# AntennaPCB.net
KiCad netlist of a schematic drawn in EAGLE
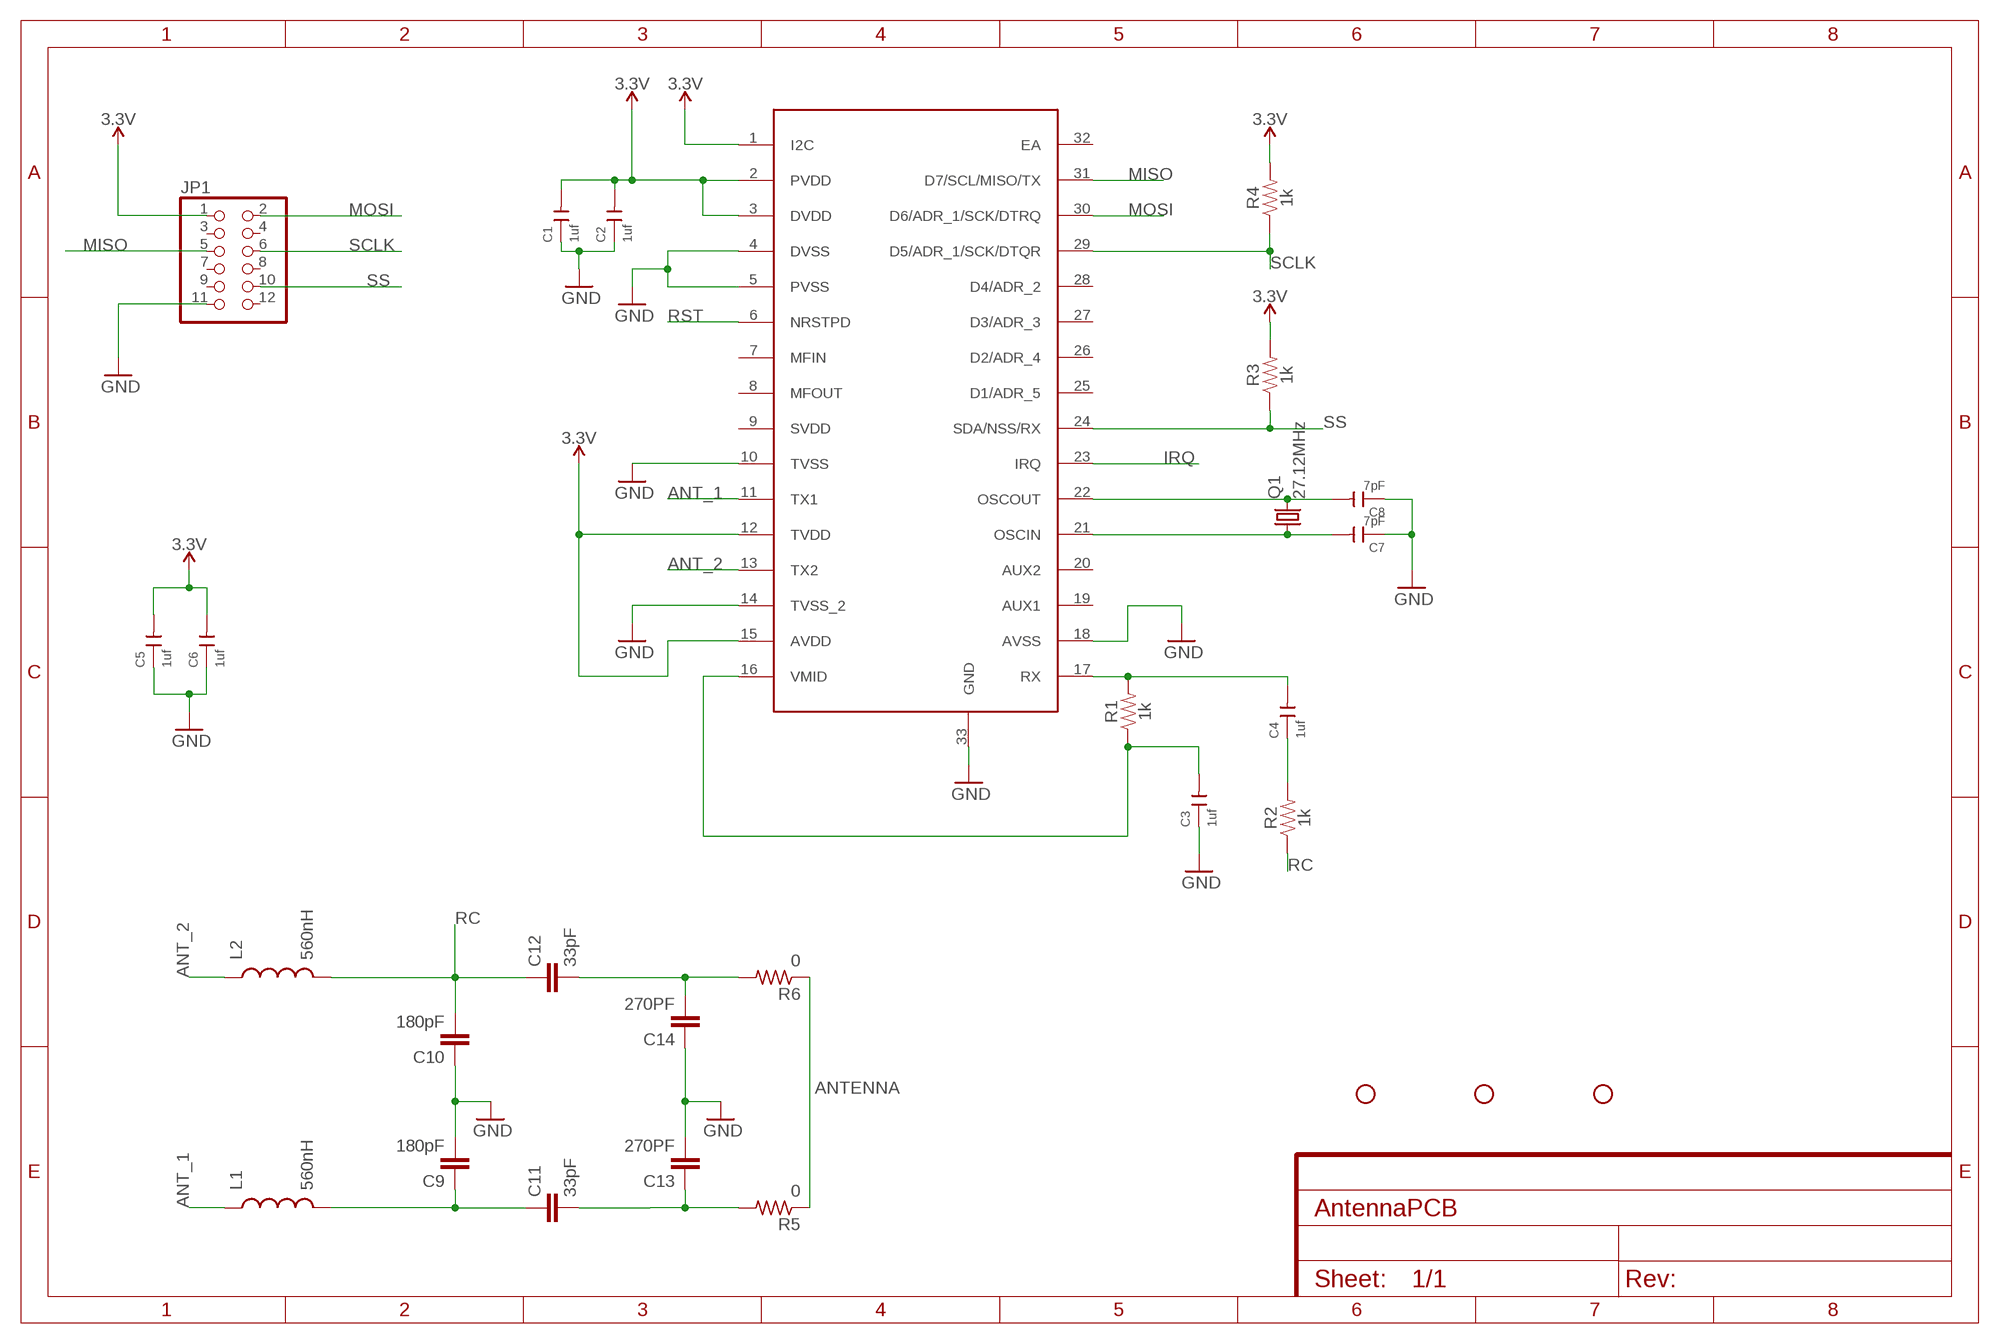
[diagram p0: schematic, sheet 1]

(export (version "E")
  (design (tool "Eeschema 10.0.6"))
  (components
    (comp (ref "C1")
      (value "1uf")
      (footprint "eagle-import:C0603")
      (fields (field (name "MPN") "CC0603KRX7R8BB105"))
      (libsource (lib "eagle-import") (part "CERAMIC-1UF-25V-10%-X7R(0603)"))
    )
    (comp (ref "C2")
      (value "1uf")
      (footprint "eagle-import:C0603")
      (fields (field (name "MPN") "CC0603KRX7R8BB105"))
      (libsource (lib "eagle-import") (part "CERAMIC-1UF-25V-10%-X7R(0603)"))
    )
    (comp (ref "C3")
      (value "1uf")
      (footprint "eagle-import:C0603")
      (fields (field (name "MPN") "CC0603KRX7R8BB105"))
      (libsource (lib "eagle-import") (part "CERAMIC-1UF-25V-10%-X7R(0603)"))
    )
    (comp (ref "C4")
      (value "1uf")
      (footprint "eagle-import:C0603")
      (fields (field (name "MPN") "CC0603KRX7R8BB105"))
      (libsource (lib "eagle-import") (part "CERAMIC-1UF-25V-10%-X7R(0603)"))
    )
    (comp (ref "C5")
      (value "1uf")
      (footprint "eagle-import:C0603")
      (fields (field (name "MPN") "CC0603KRX7R8BB105"))
      (libsource (lib "eagle-import") (part "CERAMIC-1UF-25V-10%-X7R(0603)"))
    )
    (comp (ref "C6")
      (value "1uf")
      (footprint "eagle-import:C0603")
      (fields (field (name "MPN") "CC0603KRX7R8BB105"))
      (libsource (lib "eagle-import") (part "CERAMIC-1UF-25V-10%-X7R(0603)"))
    )
    (comp (ref "C7")
      (value "7pF")
      (footprint "eagle-import:C0603")
      (fields (field (name "MPN") "CC0603KRX7R8BB105"))
      (libsource (lib "eagle-import") (part "CERAMIC-1UF-25V-10%-X7R(0603)"))
    )
    (comp (ref "C8")
      (value "7pF")
      (footprint "eagle-import:C0603")
      (fields (field (name "MPN") "CC0603KRX7R8BB105"))
      (libsource (lib "eagle-import") (part "CERAMIC-1UF-25V-10%-X7R(0603)"))
    )
    (comp (ref "C9")
      (value "180pF")
      (footprint "eagle-import:0603")
      (libsource (lib "eagle-import") (part "180PF-0603-50V-5%"))
    )
    (comp (ref "C10")
      (value "180pF")
      (footprint "eagle-import:0603")
      (libsource (lib "eagle-import") (part "180PF-0603-50V-5%"))
    )
    (comp (ref "C11")
      (value "33pF")
      (footprint "eagle-import:0603")
      (libsource (lib "eagle-import") (part "33PF-0603-50V-5%"))
    )
    (comp (ref "C12")
      (value "33pF")
      (footprint "eagle-import:0603")
      (libsource (lib "eagle-import") (part "33PF-0603-50V-5%"))
    )
    (comp (ref "C13")
      (value "270PF")
      (footprint "eagle-import:0603")
      (libsource (lib "eagle-import") (part "270PF-0603-50V-5%"))
    )
    (comp (ref "C14")
      (value "270PF")
      (footprint "eagle-import:0603")
      (libsource (lib "eagle-import") (part "270PF-0603-50V-5%"))
    )
    (comp (ref "H1")
      (value "STAND-OFF")
      (footprint "eagle-import:STAND-OFF")
      (libsource (lib "eagle-import") (part "STAND-OFF"))
    )
    (comp (ref "H2")
      (value "STAND-OFF")
      (footprint "eagle-import:STAND-OFF")
      (libsource (lib "eagle-import") (part "STAND-OFF"))
    )
    (comp (ref "H3")
      (value "STAND-OFF")
      (footprint "eagle-import:STAND-OFF")
      (libsource (lib "eagle-import") (part "STAND-OFF"))
    )
    (comp (ref "JP1")
      (value "PINHD-2X6")
      (footprint "eagle-import:2X06")
      (libsource (lib "eagle-import") (part "PINHD-2X6"))
    )
    (comp (ref "L1")
      (value "560nH")
      (footprint "eagle-import:L0603")
      (libsource (lib "eagle-import") (part "INDUCTOR"))
    )
    (comp (ref "L2")
      (value "560nH")
      (footprint "eagle-import:L0603")
      (libsource (lib "eagle-import") (part "INDUCTOR"))
    )
    (comp (ref "Q1")
      (value "27.12MHz")
      (footprint "eagle-import:HC49_S")
      (libsource (lib "eagle-import") (part "CRYSTALHC49S"))
    )
    (comp (ref "R1")
      (value "1k")
      (footprint "eagle-import:0603")
      (libsource (lib "eagle-import") (part "1KOHM-0603-1/10W-1%"))
    )
    (comp (ref "R2")
      (value "1k")
      (footprint "eagle-import:0603")
      (libsource (lib "eagle-import") (part "1KOHM-0603-1/10W-1%"))
    )
    (comp (ref "R3")
      (value "1k")
      (footprint "eagle-import:0603")
      (libsource (lib "eagle-import") (part "1KOHM-0603-1/10W-1%"))
    )
    (comp (ref "R4")
      (value "1k")
      (footprint "eagle-import:0603")
      (libsource (lib "eagle-import") (part "1KOHM-0603-1/10W-1%"))
    )
    (comp (ref "R5")
      (value "0")
      (footprint "eagle-import:RES_1206")
      (fields
        (field (name "DIGIKEY_PART_NUMBER") "P0.0ETR-ND")
        (field (name "MANUFACTURER") "Panasonic Electronic Components")
        (field (name "MPN") "ERJ-8GEY0R00V")
        (field (name "CREATED_BY") "PCBLayout.com")
      )
      (libsource (lib "eagle-import") (part "ERJ-8GEY0R00V"))
    )
    (comp (ref "R6")
      (value "0")
      (footprint "eagle-import:RES_1206")
      (fields
        (field (name "DIGIKEY_PART_NUMBER") "P0.0ETR-ND")
        (field (name "MANUFACTURER") "Panasonic Electronic Components")
        (field (name "MPN") "ERJ-8GEY0R00V")
        (field (name "CREATED_BY") "PCBLayout.com")
      )
      (libsource (lib "eagle-import") (part "ERJ-8GEY0R00V"))
    )
    (comp (ref "U$1")
      (value "MFRC522")
      (footprint "eagle-import:HVQFN32")
      (libsource (lib "eagle-import") (part "MFRC522"))
    )
  )
  (nets
    (net (code "1") (name "/ANTENNA") (class "Default")
      (node (ref "R5") (pin "1") (pinfunction "1_1") (pintype "passive"))
      (node (ref "R6") (pin "1") (pinfunction "1_1") (pintype "passive"))
    )
    (net (code "2") (name "/ANT_1") (class "Default")
      (node (ref "L1") (pin "1") (pinfunction "1_1") (pintype "passive"))
      (node (ref "U$1") (pin "11") (pinfunction "TX1_11") (pintype "bidirectional"))
    )
    (net (code "3") (name "/ANT_2") (class "Default")
      (node (ref "L2") (pin "1") (pinfunction "1_1") (pintype "passive"))
      (node (ref "U$1") (pin "13") (pinfunction "TX2_13") (pintype "bidirectional"))
    )
    (net (code "4") (name "/IRQ") (class "Default")
      (node (ref "U$1") (pin "23") (pinfunction "IRQ_23") (pintype "bidirectional"))
    )
    (net (code "5") (name "/MISO") (class "Default")
      (node (ref "JP1") (pin "5") (pinfunction "5_5") (pintype "passive"))
      (node (ref "U$1") (pin "31") (pinfunction "D7/SCL/MISO/TX_31") (pintype "bidirectional"))
    )
    (net (code "6") (name "/MOSI") (class "Default")
      (node (ref "JP1") (pin "2") (pinfunction "2_2") (pintype "passive"))
      (node (ref "U$1") (pin "30") (pinfunction "D6/ADR_1/SCK/DTRQ_30") (pintype "bidirectional"))
    )
    (net (code "7") (name "/RC") (class "Default")
      (node (ref "C10") (pin "2") (pinfunction "2_2") (pintype "passive"))
      (node (ref "C12") (pin "1") (pinfunction "1_1") (pintype "passive"))
      (node (ref "L2") (pin "2") (pinfunction "2_2") (pintype "passive"))
      (node (ref "R2") (pin "1") (pinfunction "1_1") (pintype "passive"))
    )
    (net (code "8") (name "/RST") (class "Default")
      (node (ref "U$1") (pin "6") (pinfunction "NRSTPD_6") (pintype "bidirectional"))
    )
    (net (code "9") (name "/SCLK") (class "Default")
      (node (ref "JP1") (pin "6") (pinfunction "6_6") (pintype "passive"))
      (node (ref "R4") (pin "1") (pinfunction "1_1") (pintype "passive"))
      (node (ref "U$1") (pin "29") (pinfunction "D5/ADR_1/SCK/DTQR_29") (pintype "bidirectional"))
    )
    (net (code "10") (name "/SS") (class "Default")
      (node (ref "JP1") (pin "10") (pinfunction "10_10") (pintype "passive"))
      (node (ref "R3") (pin "1") (pinfunction "1_1") (pintype "passive"))
      (node (ref "U$1") (pin "24") (pinfunction "SDA/NSS/RX_24") (pintype "bidirectional"))
    )
    (net (code "11") (name "3.3V") (class "Default")
      (node (ref "C1") (pin "2") (pinfunction "2_2") (pintype "passive"))
      (node (ref "C2") (pin "2") (pinfunction "2_2") (pintype "passive"))
      (node (ref "C5") (pin "2") (pinfunction "2_2") (pintype "passive"))
      (node (ref "C6") (pin "2") (pinfunction "2_2") (pintype "passive"))
      (node (ref "JP1") (pin "1") (pinfunction "1_1") (pintype "passive"))
      (node (ref "R3") (pin "2") (pinfunction "2_2") (pintype "passive"))
      (node (ref "R4") (pin "2") (pinfunction "2_2") (pintype "passive"))
      (node (ref "U$1") (pin "1") (pinfunction "I2C_1") (pintype "bidirectional"))
      (node (ref "U$1") (pin "12") (pinfunction "TVDD_12") (pintype "bidirectional"))
      (node (ref "U$1") (pin "15") (pinfunction "AVDD_15") (pintype "bidirectional"))
      (node (ref "U$1") (pin "2") (pinfunction "PVDD_2") (pintype "bidirectional"))
      (node (ref "U$1") (pin "3") (pinfunction "DVDD_3") (pintype "bidirectional"))
    )
    (net (code "12") (name "GND") (class "Default")
      (node (ref "C1") (pin "1") (pinfunction "1_1") (pintype "passive"))
      (node (ref "C10") (pin "1") (pinfunction "1_1") (pintype "passive"))
      (node (ref "C13") (pin "2") (pinfunction "2_2") (pintype "passive"))
      (node (ref "C14") (pin "1") (pinfunction "1_1") (pintype "passive"))
      (node (ref "C2") (pin "1") (pinfunction "1_1") (pintype "passive"))
      (node (ref "C3") (pin "1") (pinfunction "1_1") (pintype "passive"))
      (node (ref "C5") (pin "1") (pinfunction "1_1") (pintype "passive"))
      (node (ref "C6") (pin "1") (pinfunction "1_1") (pintype "passive"))
      (node (ref "C7") (pin "1") (pinfunction "1_1") (pintype "passive"))
      (node (ref "C8") (pin "1") (pinfunction "1_1") (pintype "passive"))
      (node (ref "C9") (pin "2") (pinfunction "2_2") (pintype "passive"))
      (node (ref "JP1") (pin "11") (pinfunction "11_11") (pintype "passive"))
      (node (ref "U$1") (pin "10") (pinfunction "TVSS_10") (pintype "bidirectional"))
      (node (ref "U$1") (pin "14") (pinfunction "TVSS_2_14") (pintype "bidirectional"))
      (node (ref "U$1") (pin "18") (pinfunction "AVSS_18") (pintype "bidirectional"))
      (node (ref "U$1") (pin "33") (pinfunction "GND_33") (pintype "bidirectional"))
      (node (ref "U$1") (pin "4") (pinfunction "DVSS_4") (pintype "bidirectional"))
      (node (ref "U$1") (pin "5") (pinfunction "PVSS_5") (pintype "bidirectional"))
    )
    (net (code "13") (name "Net-(C4-Pad1)") (class "Default")
      (node (ref "C4") (pin "1") (pinfunction "1_1") (pintype "passive"))
      (node (ref "R2") (pin "2") (pinfunction "2_2") (pintype "passive"))
    )
    (net (code "14") (name "Net-(C11-Pad1)") (class "Default")
      (node (ref "C11") (pin "1") (pinfunction "1_1") (pintype "passive"))
      (node (ref "C9") (pin "1") (pinfunction "1_1") (pintype "passive"))
      (node (ref "L1") (pin "2") (pinfunction "2_2") (pintype "passive"))
    )
    (net (code "15") (name "Net-(C11-Pad2)") (class "Default")
      (node (ref "C11") (pin "2") (pinfunction "2_2") (pintype "passive"))
      (node (ref "C13") (pin "1") (pinfunction "1_1") (pintype "passive"))
      (node (ref "R5") (pin "2") (pinfunction "2_2") (pintype "passive"))
    )
    (net (code "16") (name "Net-(C12-Pad2)") (class "Default")
      (node (ref "C12") (pin "2") (pinfunction "2_2") (pintype "passive"))
      (node (ref "C14") (pin "2") (pinfunction "2_2") (pintype "passive"))
      (node (ref "R6") (pin "2") (pinfunction "2_2") (pintype "passive"))
    )
    (net (code "17") (name "Net-(U$1-OSCIN)") (class "Default")
      (node (ref "C7") (pin "2") (pinfunction "2_2") (pintype "passive"))
      (node (ref "Q1") (pin "1") (pinfunction "1_1") (pintype "passive"))
      (node (ref "U$1") (pin "21") (pinfunction "OSCIN_21") (pintype "bidirectional"))
    )
    (net (code "18") (name "Net-(U$1-OSCOUT)") (class "Default")
      (node (ref "C8") (pin "2") (pinfunction "2_2") (pintype "passive"))
      (node (ref "Q1") (pin "2") (pinfunction "2_2") (pintype "passive"))
      (node (ref "U$1") (pin "22") (pinfunction "OSCOUT_22") (pintype "bidirectional"))
    )
    (net (code "19") (name "Net-(U$1-RX)") (class "Default")
      (node (ref "C4") (pin "2") (pinfunction "2_2") (pintype "passive"))
      (node (ref "R1") (pin "2") (pinfunction "2_2") (pintype "passive"))
      (node (ref "U$1") (pin "17") (pinfunction "RX_17") (pintype "bidirectional"))
    )
    (net (code "20") (name "Net-(U$1-VMID)") (class "Default")
      (node (ref "C3") (pin "2") (pinfunction "2_2") (pintype "passive"))
      (node (ref "R1") (pin "1") (pinfunction "1_1") (pintype "passive"))
      (node (ref "U$1") (pin "16") (pinfunction "VMID_16") (pintype "bidirectional"))
    )
    (net (code "21") (name "unconnected-(JP1-Pad3)") (class "Default")
      (node (ref "JP1") (pin "3") (pinfunction "3_3") (pintype "passive"))
    )
    (net (code "22") (name "unconnected-(JP1-Pad4)") (class "Default")
      (node (ref "JP1") (pin "4") (pinfunction "4_4") (pintype "passive"))
    )
    (net (code "23") (name "unconnected-(JP1-Pad7)") (class "Default")
      (node (ref "JP1") (pin "7") (pinfunction "7_7") (pintype "passive"))
    )
    (net (code "24") (name "unconnected-(JP1-Pad8)") (class "Default")
      (node (ref "JP1") (pin "8") (pinfunction "8_8") (pintype "passive"))
    )
    (net (code "25") (name "unconnected-(JP1-Pad9)") (class "Default")
      (node (ref "JP1") (pin "9") (pinfunction "9_9") (pintype "passive"))
    )
    (net (code "26") (name "unconnected-(JP1-Pad12)") (class "Default")
      (node (ref "JP1") (pin "12") (pinfunction "12_12") (pintype "passive"))
    )
    (net (code "27") (name "unconnected-(U$1-AUX1-Pad19)") (class "Default")
      (node (ref "U$1") (pin "19") (pinfunction "AUX1_19") (pintype "bidirectional"))
    )
    (net (code "28") (name "unconnected-(U$1-AUX2-Pad20)") (class "Default")
      (node (ref "U$1") (pin "20") (pinfunction "AUX2_20") (pintype "bidirectional"))
    )
    (net (code "29") (name "unconnected-(U$1-D1{slash}ADR_5-Pad25)") (class "Default")
      (node (ref "U$1") (pin "25") (pinfunction "D1/ADR_5_25") (pintype "bidirectional"))
    )
    (net (code "30") (name "unconnected-(U$1-D2{slash}ADR_4-Pad26)") (class "Default")
      (node (ref "U$1") (pin "26") (pinfunction "D2/ADR_4_26") (pintype "bidirectional"))
    )
    (net (code "31") (name "unconnected-(U$1-D3{slash}ADR_3-Pad27)") (class "Default")
      (node (ref "U$1") (pin "27") (pinfunction "D3/ADR_3_27") (pintype "bidirectional"))
    )
    (net (code "32") (name "unconnected-(U$1-D4{slash}ADR_2-Pad28)") (class "Default")
      (node (ref "U$1") (pin "28") (pinfunction "D4/ADR_2_28") (pintype "bidirectional"))
    )
    (net (code "33") (name "unconnected-(U$1-EA-Pad32)") (class "Default")
      (node (ref "U$1") (pin "32") (pinfunction "EA_32") (pintype "bidirectional"))
    )
    (net (code "34") (name "unconnected-(U$1-MFIN-Pad7)") (class "Default")
      (node (ref "U$1") (pin "7") (pinfunction "MFIN_7") (pintype "bidirectional"))
    )
    (net (code "35") (name "unconnected-(U$1-MFOUT-Pad8)") (class "Default")
      (node (ref "U$1") (pin "8") (pinfunction "MFOUT_8") (pintype "bidirectional"))
    )
    (net (code "36") (name "unconnected-(U$1-SVDD-Pad9)") (class "Default")
      (node (ref "U$1") (pin "9") (pinfunction "SVDD_9") (pintype "bidirectional"))
    )
  )
)
